# Magnetics.net
KiCad netlist of a schematic drawn in Altium Designer
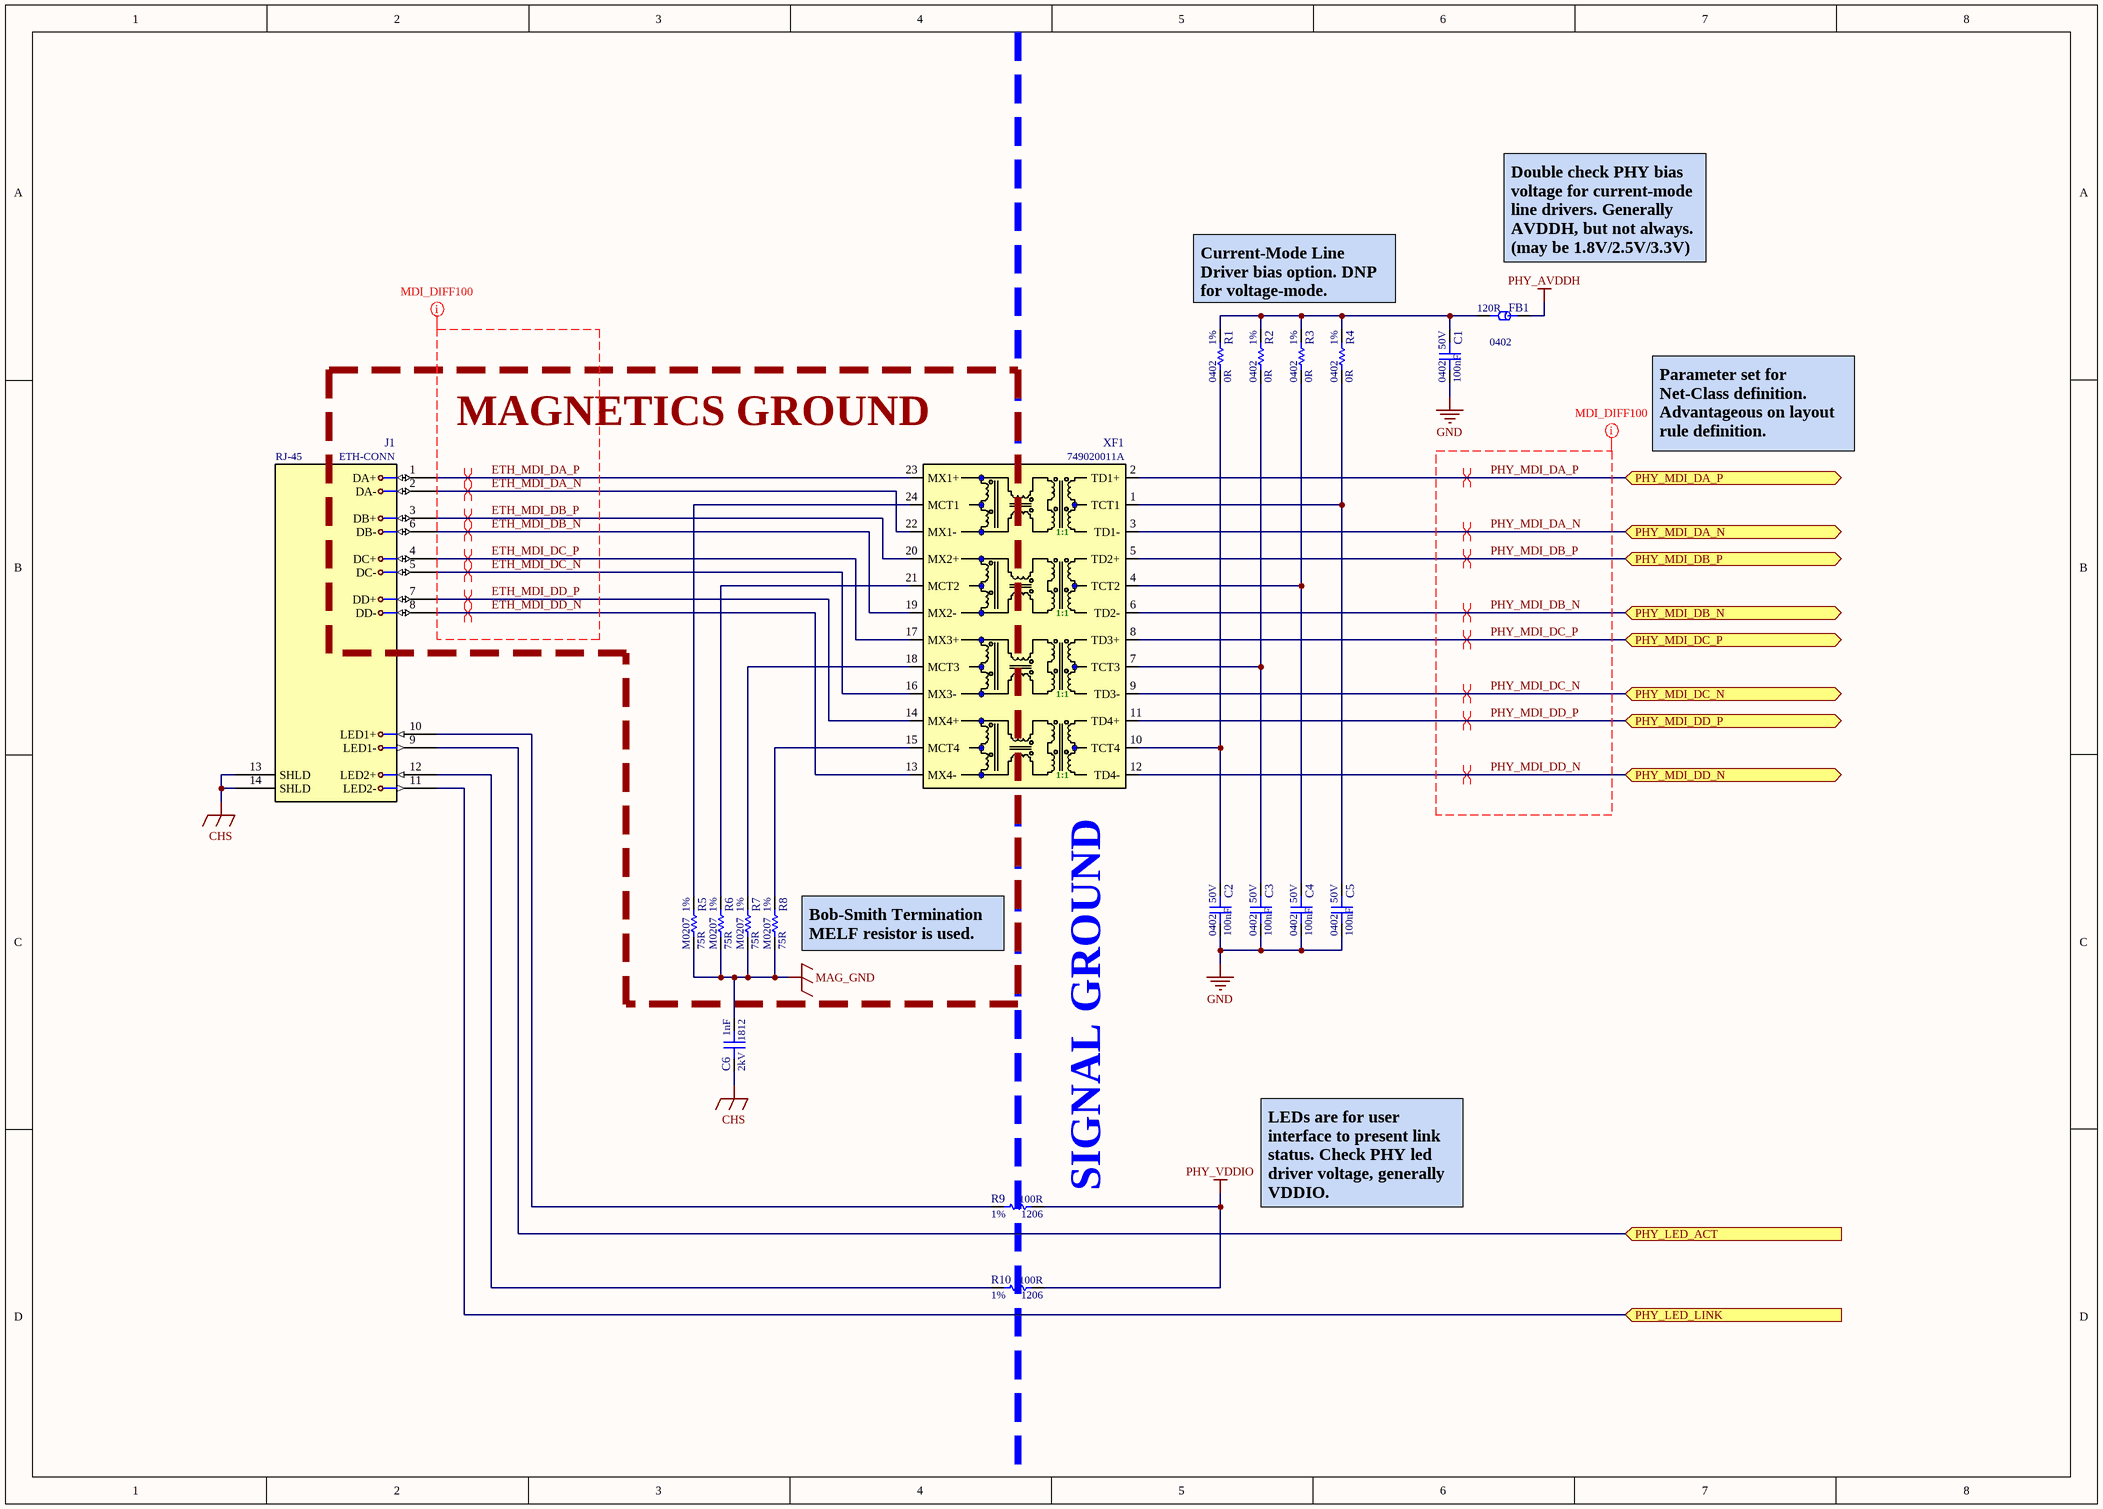
[diagram p0: Magnetics.SchDoc]

(export (version "E")
  (design (tool "Eeschema 10.0.6"))
  (components
    (comp (ref "C1")
      (value "100nF")
      (footprint "C_0402_GEN_0.70H")
      (description "CAP_CER_100nF_50V_X7R_10%_0402")
      (fields
        (field (name "VOLTAGE") "50V")
        (field (name "PACKAGE") "0402")
        (field (name "TOLERANCE") "10%")
        (field (name "Comment") "Capacitor")
      )
      (libsource (lib "BNA_HwLibDB") (part "Capacitor"))
    )
    (comp (ref "C2")
      (value "100nF")
      (footprint "C_0402_GEN_0.70H")
      (description "CAP_CER_100nF_50V_X7R_10%_0402")
      (fields
        (field (name "VOLTAGE") "50V")
        (field (name "PACKAGE") "0402")
        (field (name "TOLERANCE") "10%")
        (field (name "Comment") "Capacitor")
      )
      (libsource (lib "BNA_HwLibDB") (part "Capacitor"))
    )
    (comp (ref "C3")
      (value "100nF")
      (footprint "C_0402_GEN_0.70H")
      (description "CAP_CER_100nF_50V_X7R_10%_0402")
      (fields
        (field (name "VOLTAGE") "50V")
        (field (name "PACKAGE") "0402")
        (field (name "TOLERANCE") "10%")
        (field (name "Comment") "Capacitor")
      )
      (libsource (lib "BNA_HwLibDB") (part "Capacitor"))
    )
    (comp (ref "C4")
      (value "100nF")
      (footprint "C_0402_GEN_0.70H")
      (description "CAP_CER_100nF_50V_X7R_10%_0402")
      (fields
        (field (name "VOLTAGE") "50V")
        (field (name "PACKAGE") "0402")
        (field (name "TOLERANCE") "10%")
        (field (name "Comment") "Capacitor")
      )
      (libsource (lib "BNA_HwLibDB") (part "Capacitor"))
    )
    (comp (ref "C5")
      (value "100nF")
      (footprint "C_0402_GEN_0.70H")
      (description "CAP_CER_100nF_50V_X7R_10%_0402")
      (fields
        (field (name "VOLTAGE") "50V")
        (field (name "PACKAGE") "0402")
        (field (name "TOLERANCE") "10%")
        (field (name "Comment") "Capacitor")
      )
      (libsource (lib "BNA_HwLibDB") (part "Capacitor"))
    )
    (comp (ref "C6")
      (value "1nF")
      (footprint "C_1812_MED-N_1.55H")
      (description "CAP_CER_1nF_2KV_X7R_10%_1812")
      (fields
        (field (name "VOLTAGE") "2kV")
        (field (name "PACKAGE") "1812")
        (field (name "TOLERANCE") "10%")
        (field (name "Comment") "Capacitor")
      )
      (libsource (lib "BNA_HwLibDB") (part "Capacitor"))
    )
    (comp (ref "FB1")
      (value "120R")
      (footprint "FB_0402_GEN_0.55h")
      (description "IND_FER_120R@100M_1.3A_25%_0402")
      (fields (field (name "PACKAGE") "0402") (field (name "TOLERANCE") "±25%") (field (name "VOLTAGE") "X"))
      (libsource (lib "BNA_HwLibDB") (part "FerriteBead"))
    )
    (comp (ref "J1")
      (value "ETH-CONN")
      (fields (field (name "PACKAGE") "RJ-45") (field (name "Comment") "B2C_ETH_JACK_#2"))
      (libsource (lib "B2C_ETH_JACK_#2") (part "B2C_ETH_JACK_#2"))
    )
    (comp (ref "R1")
      (value "0R")
      (footprint "R_0402_GEN_0.40H")
      (description "RES_STD_100R_0.063W_1%_100ppm_0402")
      (fields
        (field (name "TOLERANCE") "1%")
        (field (name "PACKAGE") "0402")
        (field (name "VOLTAGE") "50V")
        (field (name "Comment") "StandardResistor")
      )
      (libsource (lib "BNA_HwLibDB") (part "StandardResistor"))
    )
    (comp (ref "R2")
      (value "0R")
      (footprint "R_0402_GEN_0.40H")
      (description "RES_STD_100R_0.063W_1%_100ppm_0402")
      (fields
        (field (name "TOLERANCE") "1%")
        (field (name "PACKAGE") "0402")
        (field (name "VOLTAGE") "50V")
        (field (name "Comment") "StandardResistor")
      )
      (libsource (lib "BNA_HwLibDB") (part "StandardResistor"))
    )
    (comp (ref "R3")
      (value "0R")
      (footprint "R_0402_GEN_0.40H")
      (description "RES_STD_100R_0.063W_1%_100ppm_0402")
      (fields
        (field (name "TOLERANCE") "1%")
        (field (name "PACKAGE") "0402")
        (field (name "VOLTAGE") "50V")
        (field (name "Comment") "StandardResistor")
      )
      (libsource (lib "BNA_HwLibDB") (part "StandardResistor"))
    )
    (comp (ref "R4")
      (value "0R")
      (footprint "R_0402_GEN_0.40H")
      (description "RES_STD_100R_0.063W_1%_100ppm_0402")
      (fields
        (field (name "TOLERANCE") "1%")
        (field (name "PACKAGE") "0402")
        (field (name "VOLTAGE") "50V")
        (field (name "Comment") "StandardResistor")
      )
      (libsource (lib "BNA_HwLibDB") (part "StandardResistor"))
    )
    (comp (ref "R5")
      (value "75R")
      (footprint "MELF_0207_GEN_2.4H")
      (description "RES_STD_75R_1W_1%_50ppm_MELF-0207")
      (fields
        (field (name "TOLERANCE") "1%")
        (field (name "PACKAGE") "M0207")
        (field (name "VOLTAGE") "350V")
        (field (name "Comment") "StandardResistor")
      )
      (libsource (lib "BNA_HwLibDB") (part "StandardResistor"))
    )
    (comp (ref "R6")
      (value "75R")
      (footprint "MELF_0207_GEN_2.4H")
      (description "RES_STD_75R_1W_1%_50ppm_MELF-0207")
      (fields
        (field (name "TOLERANCE") "1%")
        (field (name "PACKAGE") "M0207")
        (field (name "VOLTAGE") "350V")
        (field (name "Comment") "StandardResistor")
      )
      (libsource (lib "BNA_HwLibDB") (part "StandardResistor"))
    )
    (comp (ref "R7")
      (value "75R")
      (footprint "MELF_0207_GEN_2.4H")
      (description "RES_STD_75R_1W_1%_50ppm_MELF-0207")
      (fields
        (field (name "TOLERANCE") "1%")
        (field (name "PACKAGE") "M0207")
        (field (name "VOLTAGE") "350V")
        (field (name "Comment") "StandardResistor")
      )
      (libsource (lib "BNA_HwLibDB") (part "StandardResistor"))
    )
    (comp (ref "R8")
      (value "75R")
      (footprint "MELF_0207_GEN_2.4H")
      (description "RES_STD_75R_1W_1%_50ppm_MELF-0207")
      (fields
        (field (name "TOLERANCE") "1%")
        (field (name "PACKAGE") "M0207")
        (field (name "VOLTAGE") "350V")
        (field (name "Comment") "StandardResistor")
      )
      (libsource (lib "BNA_HwLibDB") (part "StandardResistor"))
    )
    (comp (ref "R9")
      (value "100R")
      (footprint "R_0402_GEN_0.40H")
      (description "RES_STD_100R_0.063W_1%_100ppm_0402")
      (fields
        (field (name "TOLERANCE") "1%")
        (field (name "PACKAGE") "1206")
        (field (name "VOLTAGE") "50V")
        (field (name "Comment") "StandardResistor")
      )
      (libsource (lib "BNA_HwLibDB") (part "StandardResistor"))
    )
    (comp (ref "R10")
      (value "100R")
      (footprint "R_0402_GEN_0.40H")
      (description "RES_STD_100R_0.063W_1%_100ppm_0402")
      (fields
        (field (name "TOLERANCE") "1%")
        (field (name "PACKAGE") "1206")
        (field (name "VOLTAGE") "50V")
        (field (name "Comment") "StandardResistor")
      )
      (libsource (lib "BNA_HwLibDB") (part "StandardResistor"))
    )
    (comp (ref "XF1")
      (value "749020011A")
      (description "Gigabit Ethernet xformer")
      (fields (field (name "Comment") "GigEthXformer"))
      (libsource (lib "GigEthXformer") (part "GigEthXformer"))
    )
  )
  (nets
    (net (code "1") (name "/ETH_MDI_DA_N") (class "Default")
      (node (ref "J1") (pin "2") (pinfunction "DA-_2") (pintype "bidirectional"))
      (node (ref "XF1") (pin "22") (pinfunction "MX1-_22") (pintype "passive"))
    )
    (net (code "2") (name "/ETH_MDI_DA_P") (class "Default")
      (node (ref "J1") (pin "1") (pinfunction "DA+_1") (pintype "bidirectional"))
      (node (ref "XF1") (pin "23") (pinfunction "MX1+_23") (pintype "passive"))
    )
    (net (code "3") (name "/ETH_MDI_DB_N") (class "Default")
      (node (ref "J1") (pin "6") (pinfunction "DB-_6") (pintype "bidirectional"))
      (node (ref "XF1") (pin "19") (pinfunction "MX2-_19") (pintype "passive"))
    )
    (net (code "4") (name "/ETH_MDI_DB_P") (class "Default")
      (node (ref "J1") (pin "3") (pinfunction "DB+_3") (pintype "bidirectional"))
      (node (ref "XF1") (pin "20") (pinfunction "MX2+_20") (pintype "passive"))
    )
    (net (code "5") (name "/ETH_MDI_DC_N") (class "Default")
      (node (ref "J1") (pin "5") (pinfunction "DC-_5") (pintype "bidirectional"))
      (node (ref "XF1") (pin "16") (pinfunction "MX3-_16") (pintype "passive"))
    )
    (net (code "6") (name "/ETH_MDI_DC_P") (class "Default")
      (node (ref "J1") (pin "4") (pinfunction "DC+_4") (pintype "bidirectional"))
      (node (ref "XF1") (pin "17") (pinfunction "MX3+_17") (pintype "passive"))
    )
    (net (code "7") (name "/ETH_MDI_DD_N") (class "Default")
      (node (ref "J1") (pin "8") (pinfunction "DD-_8") (pintype "bidirectional"))
      (node (ref "XF1") (pin "13") (pinfunction "MX4-_13") (pintype "passive"))
    )
    (net (code "8") (name "/ETH_MDI_DD_P") (class "Default")
      (node (ref "J1") (pin "7") (pinfunction "DD+_7") (pintype "bidirectional"))
      (node (ref "XF1") (pin "14") (pinfunction "MX4+_14") (pintype "passive"))
    )
    (net (code "9") (name "/PHY_LED_ACT") (class "Default")
      (node (ref "J1") (pin "9") (pinfunction "LED1-_9") (pintype "output"))
    )
    (net (code "10") (name "/PHY_LED_LINK") (class "Default")
      (node (ref "J1") (pin "11") (pinfunction "LED2-_11") (pintype "output"))
    )
    (net (code "11") (name "/PHY_MDI_DA_N") (class "Default")
      (node (ref "XF1") (pin "3") (pinfunction "TD1-_3") (pintype "passive"))
    )
    (net (code "12") (name "/PHY_MDI_DA_P") (class "Default")
      (node (ref "XF1") (pin "2") (pinfunction "TD1+_2") (pintype "passive"))
    )
    (net (code "13") (name "/PHY_MDI_DB_N") (class "Default")
      (node (ref "XF1") (pin "6") (pinfunction "TD2-_6") (pintype "passive"))
    )
    (net (code "14") (name "/PHY_MDI_DB_P") (class "Default")
      (node (ref "XF1") (pin "5") (pinfunction "TD2+_5") (pintype "passive"))
    )
    (net (code "15") (name "/PHY_MDI_DC_N") (class "Default")
      (node (ref "XF1") (pin "9") (pinfunction "TD3-_9") (pintype "passive"))
    )
    (net (code "16") (name "/PHY_MDI_DC_P") (class "Default")
      (node (ref "XF1") (pin "8") (pinfunction "TD3+_8") (pintype "passive"))
    )
    (net (code "17") (name "/PHY_MDI_DD_N") (class "Default")
      (node (ref "XF1") (pin "12") (pinfunction "TD4-_12") (pintype "passive"))
    )
    (net (code "18") (name "/PHY_MDI_DD_P") (class "Default")
      (node (ref "XF1") (pin "11") (pinfunction "TD4+_11") (pintype "passive"))
    )
    (net (code "19") (name "CHS") (class "Default")
      (node (ref "C6") (pin "1") (pinfunction "1_1") (pintype "passive"))
      (node (ref "J1") (pin "13") (pinfunction "SHLD_13") (pintype "power_in"))
      (node (ref "J1") (pin "14") (pinfunction "SHLD_14") (pintype "power_in"))
    )
    (net (code "20") (name "GND") (class "Default")
      (node (ref "C1") (pin "2") (pinfunction "2_2") (pintype "passive"))
      (node (ref "C2") (pin "2") (pinfunction "2_2") (pintype "passive"))
      (node (ref "C3") (pin "2") (pinfunction "2_2") (pintype "passive"))
      (node (ref "C4") (pin "2") (pinfunction "2_2") (pintype "passive"))
      (node (ref "C5") (pin "2") (pinfunction "2_2") (pintype "passive"))
    )
    (net (code "21") (name "MAG_GND") (class "Default")
      (node (ref "C6") (pin "2") (pinfunction "2_2") (pintype "passive"))
      (node (ref "R5") (pin "2") (pinfunction "2_2") (pintype "passive"))
      (node (ref "R6") (pin "2") (pinfunction "2_2") (pintype "passive"))
      (node (ref "R7") (pin "2") (pinfunction "2_2") (pintype "passive"))
      (node (ref "R8") (pin "2") (pinfunction "2_2") (pintype "passive"))
    )
    (net (code "22") (name "Net-(C1-Pad1)") (class "Default")
      (node (ref "C1") (pin "1") (pinfunction "1_1") (pintype "passive"))
      (node (ref "FB1") (pin "2") (pinfunction "2_2") (pintype "passive"))
      (node (ref "R1") (pin "1") (pinfunction "1_1") (pintype "passive"))
      (node (ref "R2") (pin "1") (pinfunction "1_1") (pintype "passive"))
      (node (ref "R3") (pin "1") (pinfunction "1_1") (pintype "passive"))
      (node (ref "R4") (pin "1") (pinfunction "1_1") (pintype "passive"))
    )
    (net (code "23") (name "Net-(J1-LED1+)") (class "Default")
      (node (ref "J1") (pin "10") (pinfunction "LED1+_10") (pintype "input"))
      (node (ref "R9") (pin "1") (pinfunction "1_1") (pintype "passive"))
    )
    (net (code "24") (name "Net-(J1-LED2+)") (class "Default")
      (node (ref "J1") (pin "12") (pinfunction "LED2+_12") (pintype "input"))
      (node (ref "R10") (pin "1") (pinfunction "1_1") (pintype "passive"))
    )
    (net (code "25") (name "Net-(XF1-MCT1)") (class "Default")
      (node (ref "R5") (pin "1") (pinfunction "1_1") (pintype "passive"))
      (node (ref "XF1") (pin "24") (pinfunction "MCT1_24") (pintype "passive"))
    )
    (net (code "26") (name "Net-(XF1-MCT2)") (class "Default")
      (node (ref "R6") (pin "1") (pinfunction "1_1") (pintype "passive"))
      (node (ref "XF1") (pin "21") (pinfunction "MCT2_21") (pintype "passive"))
    )
    (net (code "27") (name "Net-(XF1-MCT3)") (class "Default")
      (node (ref "R7") (pin "1") (pinfunction "1_1") (pintype "passive"))
      (node (ref "XF1") (pin "18") (pinfunction "MCT3_18") (pintype "passive"))
    )
    (net (code "28") (name "Net-(XF1-MCT4)") (class "Default")
      (node (ref "R8") (pin "1") (pinfunction "1_1") (pintype "passive"))
      (node (ref "XF1") (pin "15") (pinfunction "MCT4_15") (pintype "passive"))
    )
    (net (code "29") (name "Net-(XF1-TCT1)") (class "Default")
      (node (ref "C5") (pin "1") (pinfunction "1_1") (pintype "passive"))
      (node (ref "R4") (pin "2") (pinfunction "2_2") (pintype "passive"))
      (node (ref "XF1") (pin "1") (pinfunction "TCT1_1") (pintype "passive"))
    )
    (net (code "30") (name "Net-(XF1-TCT2)") (class "Default")
      (node (ref "C4") (pin "1") (pinfunction "1_1") (pintype "passive"))
      (node (ref "R3") (pin "2") (pinfunction "2_2") (pintype "passive"))
      (node (ref "XF1") (pin "4") (pinfunction "TCT2_4") (pintype "passive"))
    )
    (net (code "31") (name "Net-(XF1-TCT3)") (class "Default")
      (node (ref "C3") (pin "1") (pinfunction "1_1") (pintype "passive"))
      (node (ref "R2") (pin "2") (pinfunction "2_2") (pintype "passive"))
      (node (ref "XF1") (pin "7") (pinfunction "TCT3_7") (pintype "passive"))
    )
    (net (code "32") (name "Net-(XF1-TCT4)") (class "Default")
      (node (ref "C2") (pin "1") (pinfunction "1_1") (pintype "passive"))
      (node (ref "R1") (pin "2") (pinfunction "2_2") (pintype "passive"))
      (node (ref "XF1") (pin "10") (pinfunction "TCT4_10") (pintype "passive"))
    )
    (net (code "33") (name "PHY_AVDDH") (class "Default")
      (node (ref "FB1") (pin "1") (pinfunction "1_1") (pintype "passive"))
    )
    (net (code "34") (name "PHY_VDDIO") (class "Default")
      (node (ref "R10") (pin "2") (pinfunction "2_2") (pintype "passive"))
      (node (ref "R9") (pin "2") (pinfunction "2_2") (pintype "passive"))
    )
  )
)
